# switcher.net
KiCad netlist of a schematic drawn in EAGLE
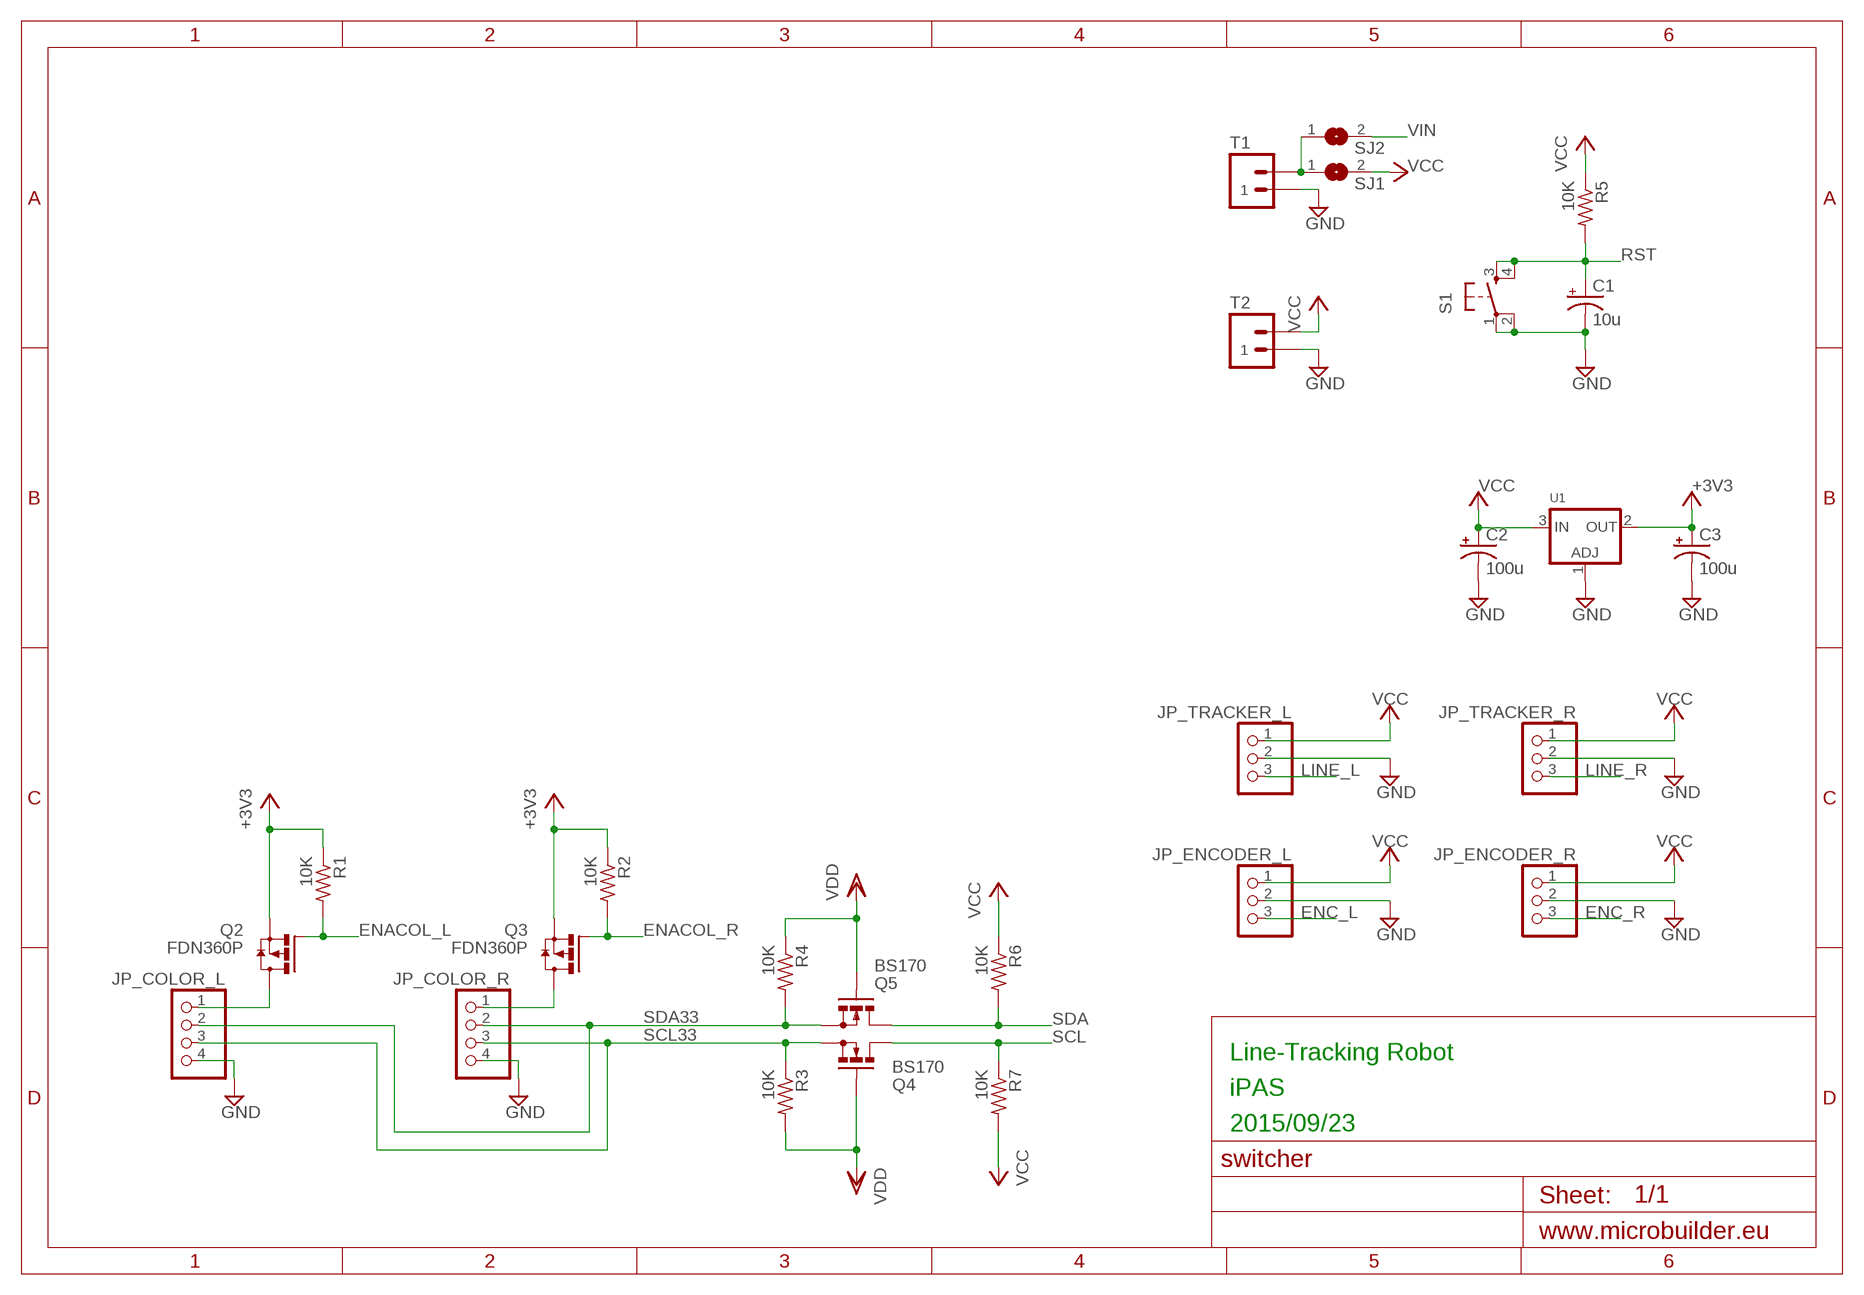
[diagram p0: schematic, sheet 1]

(export (version "E")
  (design (tool "Eeschema 10.0.6"))
  (components
    (comp (ref "C1")
      (value "10u")
      (footprint "eagle-import:RCL_E2,5-6")
      (libsource (lib "eagle-import") (part "RCL_CPOL-USE2.5-6"))
    )
    (comp (ref "C2")
      (value "100u")
      (footprint "eagle-import:RCL_E2,5-6")
      (libsource (lib "eagle-import") (part "RCL_CPOL-USE2.5-6"))
    )
    (comp (ref "C3")
      (value "100u")
      (footprint "eagle-import:RCL_E2,5-6")
      (libsource (lib "eagle-import") (part "RCL_CPOL-USE2.5-6"))
    )
    (comp (ref "JP_COLOR_L")
      (value "HEADER-1X4ROUND")
      (footprint "eagle-import:1X04_ROUND")
      (libsource (lib "eagle-import") (part "HEADER-1X4ROUND"))
    )
    (comp (ref "JP_COLOR_R")
      (value "HEADER-1X4ROUND")
      (footprint "eagle-import:1X04_ROUND")
      (libsource (lib "eagle-import") (part "HEADER-1X4ROUND"))
    )
    (comp (ref "JP_ENCODER_L")
      (value "HEADER-1X3ROUND")
      (footprint "eagle-import:1X03_ROUND")
      (libsource (lib "eagle-import") (part "HEADER-1X3ROUND"))
    )
    (comp (ref "JP_ENCODER_R")
      (value "HEADER-1X3ROUND")
      (footprint "eagle-import:1X03_ROUND")
      (libsource (lib "eagle-import") (part "HEADER-1X3ROUND"))
    )
    (comp (ref "JP_TRACKER_L")
      (value "HEADER-1X3ROUND")
      (footprint "eagle-import:1X03_ROUND")
      (libsource (lib "eagle-import") (part "HEADER-1X3ROUND"))
    )
    (comp (ref "JP_TRACKER_R")
      (value "HEADER-1X3ROUND")
      (footprint "eagle-import:1X03_ROUND")
      (libsource (lib "eagle-import") (part "HEADER-1X3ROUND"))
    )
    (comp (ref "Q2")
      (value "FDN360P")
      (footprint "eagle-import:SUPER-SOT3")
      (libsource (lib "eagle-import") (part "FDN360P"))
    )
    (comp (ref "Q3")
      (value "FDN360P")
      (footprint "eagle-import:SUPER-SOT3")
      (libsource (lib "eagle-import") (part "FDN360P"))
    )
    (comp (ref "Q4")
      (value "BS170")
      (footprint "eagle-import:TO92-")
      (libsource (lib "eagle-import") (part "BS170"))
    )
    (comp (ref "Q5")
      (value "BS170")
      (footprint "eagle-import:TO92-")
      (libsource (lib "eagle-import") (part "BS170"))
    )
    (comp (ref "R1")
      (value "10K")
      (footprint "eagle-import:RCL_0204_5")
      (libsource (lib "eagle-import") (part "RCL_R-US0204/5"))
    )
    (comp (ref "R2")
      (value "10K")
      (footprint "eagle-import:RCL_0204_5")
      (libsource (lib "eagle-import") (part "RCL_R-US0204/5"))
    )
    (comp (ref "R3")
      (value "10K")
      (footprint "eagle-import:RCL_0204_5")
      (libsource (lib "eagle-import") (part "RCL_R-US0204/5"))
    )
    (comp (ref "R4")
      (value "10K")
      (footprint "eagle-import:RCL_0204_5")
      (libsource (lib "eagle-import") (part "RCL_R-US0204/5"))
    )
    (comp (ref "R5")
      (value "10K")
      (footprint "eagle-import:RCL_0204_5")
      (libsource (lib "eagle-import") (part "RCL_R-US0204/5"))
    )
    (comp (ref "R6")
      (value "10K")
      (footprint "eagle-import:RCL_0204_5")
      (libsource (lib "eagle-import") (part "RCL_R-US0204/5"))
    )
    (comp (ref "R7")
      (value "10K")
      (footprint "eagle-import:RCL_0204_5")
      (libsource (lib "eagle-import") (part "RCL_R-US0204/5"))
    )
    (comp (ref "S1")
      (value "SWITCH-TACT_DTS-6")
      (footprint "eagle-import:SWITCH-TACT_DTS-6")
      (libsource (lib "eagle-import") (part "SWITCH-TACT_DTS-6"))
    )
    (comp (ref "SJ1")
      (value "SOLDERJUMPERREFLOW")
      (footprint "eagle-import:SOLDERJUMPER_REFLOW")
      (libsource (lib "eagle-import") (part "SOLDERJUMPERREFLOW"))
    )
    (comp (ref "SJ2")
      (value "SOLDERJUMPERREFLOW")
      (footprint "eagle-import:SOLDERJUMPER_REFLOW")
      (libsource (lib "eagle-import") (part "SOLDERJUMPERREFLOW"))
    )
    (comp (ref "T1")
      (value "ST02-3.81MM")
      (footprint "eagle-import:DG381-02P")
      (libsource (lib "eagle-import") (part "ST02-3.81MM"))
    )
    (comp (ref "T2")
      (value "ST02-3.81MM")
      (footprint "eagle-import:DG381-02P")
      (libsource (lib "eagle-import") (part "ST02-3.81MM"))
    )
    (comp (ref "U1")
      (value "LM1117SOT223-REFLOW")
      (footprint "eagle-import:SOT223-R")
      (libsource (lib "eagle-import") (part "LM1117SOT223-REFLOW"))
    )
  )
  (nets
    (net (code "1") (name "+3V3") (class "Default")
      (node (ref "C3") (pin "+") (pinfunction "+_+") (pintype "passive"))
      (node (ref "Q2") (pin "2") (pinfunction "S_2") (pintype "passive"))
      (node (ref "Q3") (pin "2") (pinfunction "S_2") (pintype "passive"))
      (node (ref "R1") (pin "1") (pinfunction "1_1") (pintype "passive"))
      (node (ref "R2") (pin "1") (pinfunction "1_1") (pintype "passive"))
      (node (ref "U1") (pin "2") (pinfunction "OUT_2") (pintype "passive"))
    )
    (net (code "2") (name "/ENACOL_L") (class "Default")
      (node (ref "Q2") (pin "1") (pinfunction "G_1") (pintype "passive"))
      (node (ref "R1") (pin "2") (pinfunction "2_2") (pintype "passive"))
    )
    (net (code "3") (name "/ENACOL_R") (class "Default")
      (node (ref "Q3") (pin "1") (pinfunction "G_1") (pintype "passive"))
      (node (ref "R2") (pin "2") (pinfunction "2_2") (pintype "passive"))
    )
    (net (code "4") (name "/ENC_L") (class "Default")
      (node (ref "JP_ENCODER_L") (pin "3") (pinfunction "3_3") (pintype "passive"))
    )
    (net (code "5") (name "/ENC_R") (class "Default")
      (node (ref "JP_ENCODER_R") (pin "3") (pinfunction "3_3") (pintype "passive"))
    )
    (net (code "6") (name "/LINE_L") (class "Default")
      (node (ref "JP_TRACKER_L") (pin "3") (pinfunction "3_3") (pintype "passive"))
    )
    (net (code "7") (name "/LINE_R") (class "Default")
      (node (ref "JP_TRACKER_R") (pin "3") (pinfunction "3_3") (pintype "passive"))
    )
    (net (code "8") (name "/RST") (class "Default")
      (node (ref "C1") (pin "+") (pinfunction "+_+") (pintype "passive"))
      (node (ref "R5") (pin "2") (pinfunction "2_2") (pintype "passive"))
      (node (ref "S1") (pin "3") (pinfunction "3_3") (pintype "passive"))
      (node (ref "S1") (pin "4") (pinfunction "4_4") (pintype "passive"))
    )
    (net (code "9") (name "/SCL") (class "Default")
      (node (ref "Q4") (pin "1") (pinfunction "D_1") (pintype "passive"))
      (node (ref "R7") (pin "1") (pinfunction "1_1") (pintype "passive"))
    )
    (net (code "10") (name "/SCL33") (class "Default")
      (node (ref "JP_COLOR_L") (pin "3") (pinfunction "3_3") (pintype "passive"))
      (node (ref "JP_COLOR_R") (pin "3") (pinfunction "3_3") (pintype "passive"))
      (node (ref "Q4") (pin "3") (pinfunction "S_3") (pintype "passive"))
      (node (ref "R3") (pin "1") (pinfunction "1_1") (pintype "passive"))
    )
    (net (code "11") (name "/SDA") (class "Default")
      (node (ref "Q5") (pin "1") (pinfunction "D_1") (pintype "passive"))
      (node (ref "R6") (pin "2") (pinfunction "2_2") (pintype "passive"))
    )
    (net (code "12") (name "/SDA33") (class "Default")
      (node (ref "JP_COLOR_L") (pin "2") (pinfunction "2_2") (pintype "passive"))
      (node (ref "JP_COLOR_R") (pin "2") (pinfunction "2_2") (pintype "passive"))
      (node (ref "Q5") (pin "3") (pinfunction "S_3") (pintype "passive"))
      (node (ref "R4") (pin "2") (pinfunction "2_2") (pintype "passive"))
    )
    (net (code "13") (name "/VIN") (class "Default")
      (node (ref "SJ2") (pin "2") (pinfunction "2_2") (pintype "passive"))
    )
    (net (code "14") (name "GND") (class "Default")
      (node (ref "C1") (pin "-") (pinfunction "-_-") (pintype "passive"))
      (node (ref "C2") (pin "-") (pinfunction "-_-") (pintype "passive"))
      (node (ref "C3") (pin "-") (pinfunction "-_-") (pintype "passive"))
      (node (ref "JP_COLOR_L") (pin "4") (pinfunction "4_4") (pintype "passive"))
      (node (ref "JP_COLOR_R") (pin "4") (pinfunction "4_4") (pintype "passive"))
      (node (ref "JP_ENCODER_L") (pin "2") (pinfunction "2_2") (pintype "passive"))
      (node (ref "JP_ENCODER_R") (pin "2") (pinfunction "2_2") (pintype "passive"))
      (node (ref "JP_TRACKER_L") (pin "2") (pinfunction "2_2") (pintype "passive"))
      (node (ref "JP_TRACKER_R") (pin "2") (pinfunction "2_2") (pintype "passive"))
      (node (ref "S1") (pin "1") (pinfunction "1_1") (pintype "passive"))
      (node (ref "S1") (pin "2") (pinfunction "2_2") (pintype "passive"))
      (node (ref "T1") (pin "1") (pinfunction "1_1") (pintype "passive"))
      (node (ref "T2") (pin "1") (pinfunction "1_1") (pintype "passive"))
      (node (ref "U1") (pin "1") (pinfunction "ADJ_1") (pintype "input"))
    )
    (net (code "15") (name "Net-(Q2-D)") (class "Default")
      (node (ref "JP_COLOR_L") (pin "1") (pinfunction "1_1") (pintype "passive"))
      (node (ref "Q2") (pin "3") (pinfunction "D_3") (pintype "passive"))
    )
    (net (code "16") (name "Net-(Q3-D)") (class "Default")
      (node (ref "JP_COLOR_R") (pin "1") (pinfunction "1_1") (pintype "passive"))
      (node (ref "Q3") (pin "3") (pinfunction "D_3") (pintype "passive"))
    )
    (net (code "17") (name "Net-(SJ1-Pad1)") (class "Default")
      (node (ref "SJ1") (pin "1") (pinfunction "1_1") (pintype "passive"))
      (node (ref "SJ2") (pin "1") (pinfunction "1_1") (pintype "passive"))
      (node (ref "T1") (pin "2") (pinfunction "2_2") (pintype "passive"))
    )
    (net (code "18") (name "VCC") (class "Default")
      (node (ref "C2") (pin "+") (pinfunction "+_+") (pintype "passive"))
      (node (ref "JP_ENCODER_L") (pin "1") (pinfunction "1_1") (pintype "passive"))
      (node (ref "JP_ENCODER_R") (pin "1") (pinfunction "1_1") (pintype "passive"))
      (node (ref "JP_TRACKER_L") (pin "1") (pinfunction "1_1") (pintype "passive"))
      (node (ref "JP_TRACKER_R") (pin "1") (pinfunction "1_1") (pintype "passive"))
      (node (ref "R5") (pin "1") (pinfunction "1_1") (pintype "passive"))
      (node (ref "R6") (pin "1") (pinfunction "1_1") (pintype "passive"))
      (node (ref "R7") (pin "2") (pinfunction "2_2") (pintype "passive"))
      (node (ref "SJ1") (pin "2") (pinfunction "2_2") (pintype "passive"))
      (node (ref "T2") (pin "2") (pinfunction "2_2") (pintype "passive"))
      (node (ref "U1") (pin "3") (pinfunction "IN_3") (pintype "input"))
    )
    (net (code "19") (name "VDD") (class "Default")
      (node (ref "Q4") (pin "2") (pinfunction "G_2") (pintype "passive"))
      (node (ref "Q5") (pin "2") (pinfunction "G_2") (pintype "passive"))
      (node (ref "R3") (pin "2") (pinfunction "2_2") (pintype "passive"))
      (node (ref "R4") (pin "1") (pinfunction "1_1") (pintype "passive"))
    )
  )
)
